# MICROCONTROLLER_RADIO.net
KiCad netlist of a schematic drawn in Altium Designer
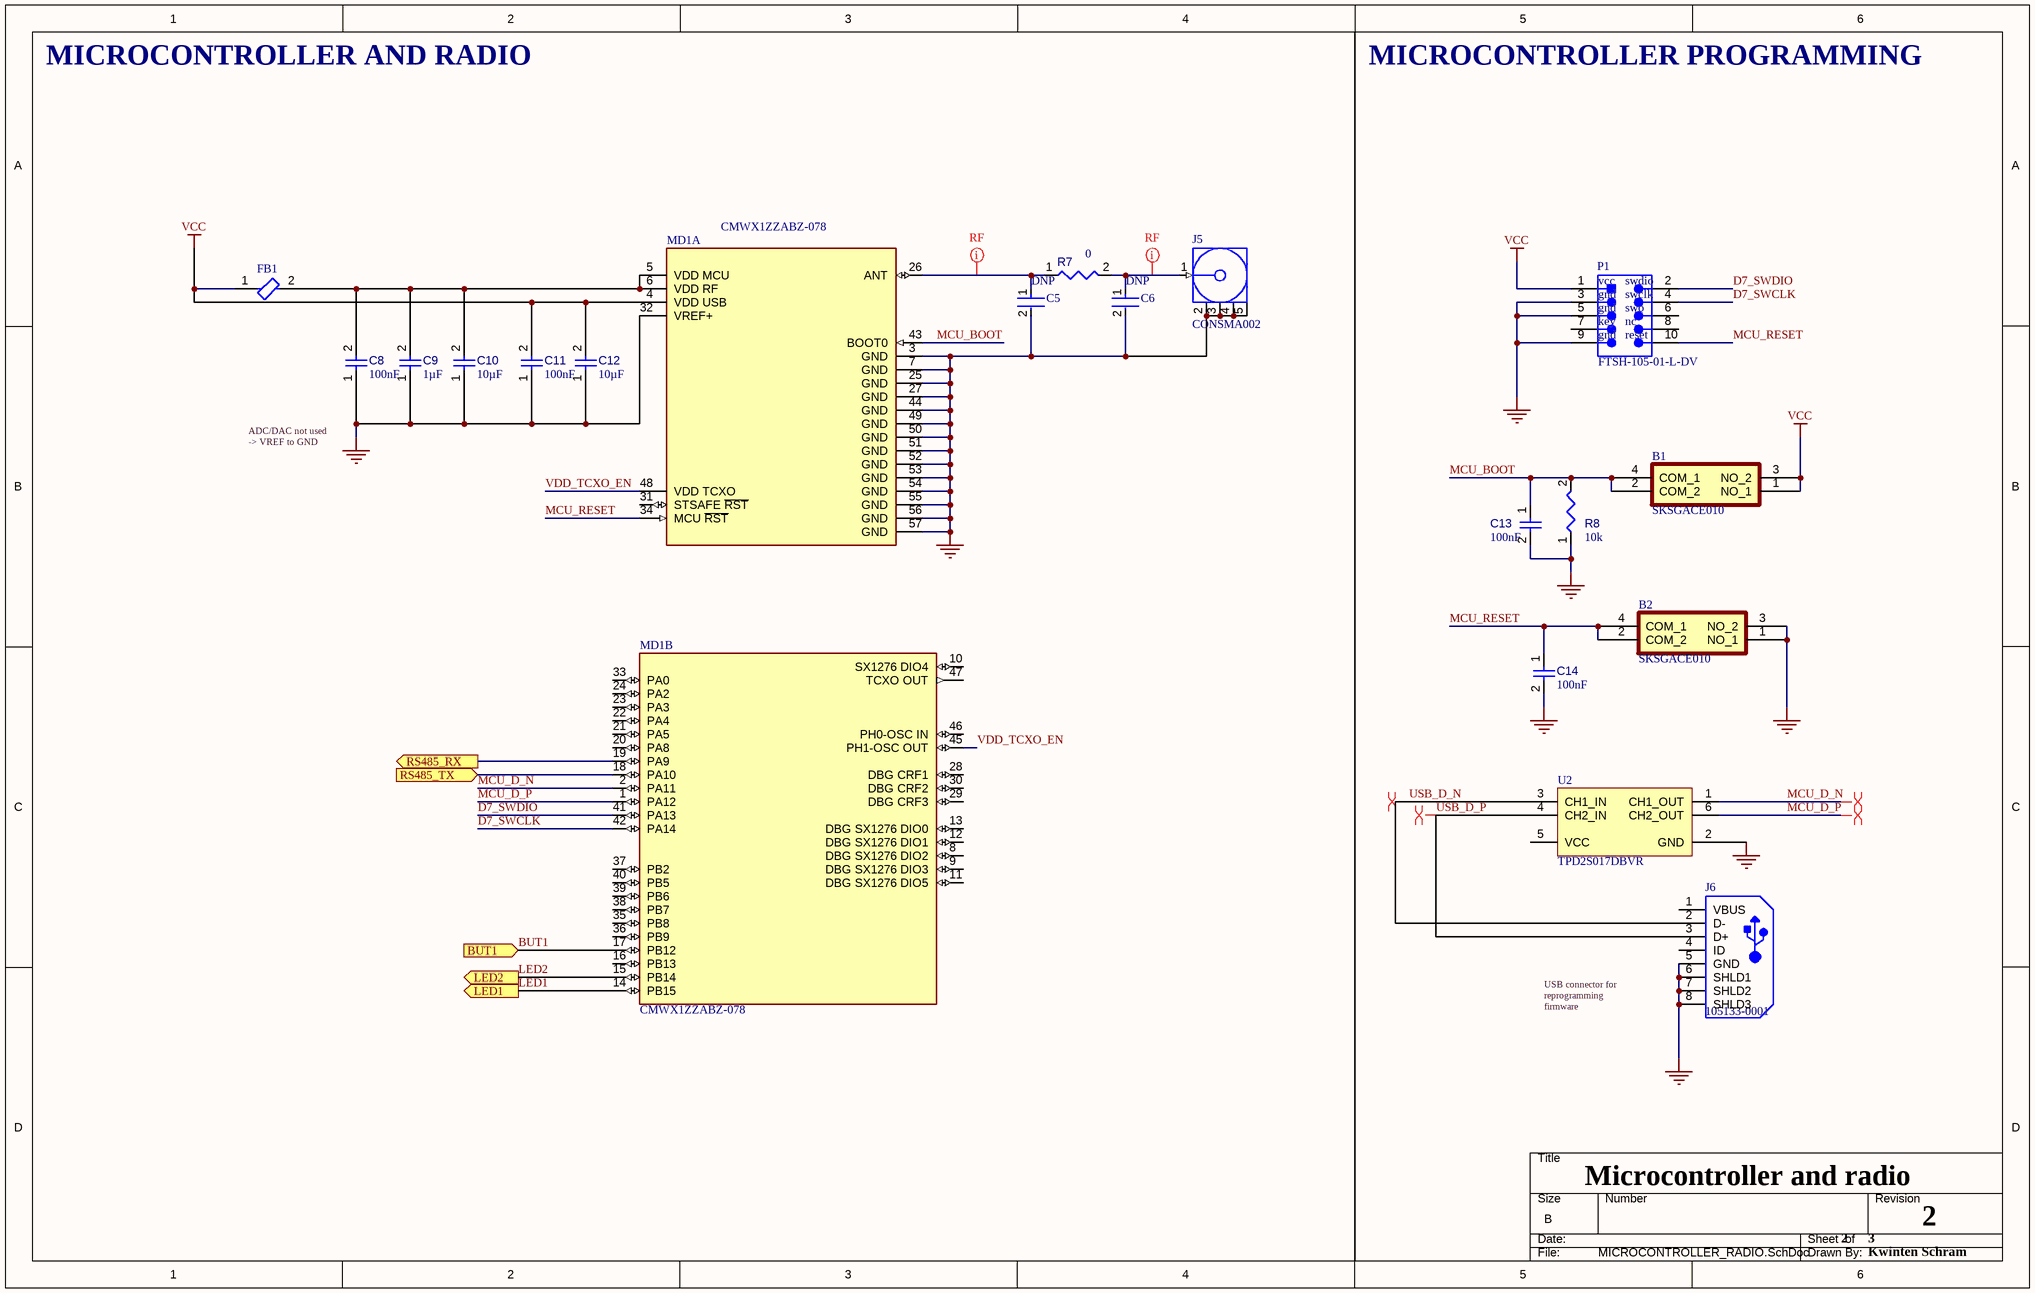
[diagram p0: MICROCONTROLLER_RADIO.SchDoc]

(export (version "E")
  (design (tool "Eeschema 10.0.6"))
  (components
    (comp (ref "B1")
      (value "SKSGACE010")
      (footprint "RKC2SJF170SMTRLFS-Footprint-1")
      (libsource (lib "Altium Concord Pro on A365") (part "RKC2SJF170SMTRLFS-Symbol-1"))
    )
    (comp (ref "B2")
      (value "SKSGACE010")
      (footprint "RKC2SJF170SMTRLFS-Footprint-1")
      (libsource (lib "Altium Concord Pro on A365") (part "RKC2SJF170SMTRLFS-Symbol-1"))
    )
    (comp (ref "C5")
      (value "CC0402KRX7R7BB104")
      (footprint "FP-CC0402-IPC_A")
      (description "CAP CER 0.1UF 16V X7R 0402")
      (fields
        (field (name "CAPACITANCE") "DNP")
        (field (name "MANUFACTURER") "YAGEO")
        (field (name "TOLERANCE") "0.1")
      )
      (libsource (lib "Altium Content Vault") (part "11868f565c42a9108669ba33697ecf6"))
    )
    (comp (ref "C6")
      (value "CC0402KRX7R7BB104")
      (footprint "FP-CC0402-IPC_A")
      (description "CAP CER 0.1UF 16V X7R 0402")
      (fields
        (field (name "CAPACITANCE") "DNP")
        (field (name "MANUFACTURER") "YAGEO")
        (field (name "TOLERANCE") "0.1")
      )
      (libsource (lib "Altium Content Vault") (part "11868f565c42a9108669ba33697ecf6"))
    )
    (comp (ref "C8")
      (value "100nF")
      (footprint "FP-0603-L_1_6_0_15-W_0_81-MFG")
      (fields (field (name "TOLERANCE") "10%") (field (name "Comment") "06033C104KAT2A"))
      (libsource (lib "Altium Concord Pro on A365") (part "CAP-NP-2"))
    )
    (comp (ref "C9")
      (value "1µF")
      (footprint "FP-CC0603-DA-MFG")
      (fields (field (name "TOLERANCE") "10%") (field (name "Comment") "CC0603KPX7R8BB105"))
      (libsource (lib "Altium Concord Pro on A365") (part "CAP-NP-2"))
    )
    (comp (ref "C10")
      (value "10µF")
      (footprint "FP-GRM188-0_1-e0_2_0_55-MFG")
      (fields (field (name "TOLERANCE") "20%") (field (name "Comment") "GRM188R60J106ME47D"))
      (libsource (lib "Altium Concord Pro on A365") (part "CAP-NP-2"))
    )
    (comp (ref "C11")
      (value "100nF")
      (footprint "FP-0603-L_1_6_0_15-W_0_81-MFG")
      (fields (field (name "TOLERANCE") "10%") (field (name "Comment") "06033C104KAT2A"))
      (libsource (lib "Altium Concord Pro on A365") (part "CAP-NP-2"))
    )
    (comp (ref "C12")
      (value "10µF")
      (footprint "FP-GRM188-0_1-e0_2_0_55-MFG")
      (fields (field (name "TOLERANCE") "20%") (field (name "Comment") "GRM188R60J106ME47D"))
      (libsource (lib "Altium Concord Pro on A365") (part "CAP-NP-2"))
    )
    (comp (ref "C13")
      (value "100nF")
      (footprint "FP-0603-L_1_6_0_15-W_0_81-MFG")
      (fields (field (name "TOLERANCE") "10%") (field (name "Comment") "06033C104KAT2A"))
      (libsource (lib "Altium Concord Pro on A365") (part "CAP-NP-2"))
    )
    (comp (ref "C14")
      (value "100nF")
      (footprint "FP-0603-L_1_6_0_15-W_0_81-MFG")
      (fields (field (name "TOLERANCE") "10%") (field (name "Comment") "06033C104KAT2A"))
      (libsource (lib "Altium Concord Pro on A365") (part "CAP-NP-2"))
    )
    (comp (ref "FB1")
      (value "BLM18AG121SN1D")
      (footprint "FP-BLM18-0_15-t0_8-IPC_B")
      (description "Chip Ferrite Bead, 0603, 120Ω @ 100MHz, 0.18Ω, 25%, 800mA")
      (fields (field (name "TOLERANCE") "25%"))
      (libsource (lib "Altium Content Vault") (part "5f30dd21d616792df468990f7003faa"))
    )
    (comp (ref "J5")
      (value "CONSMA002")
      (footprint "CON-REVSMA-RA")
      (description "RF SMA Connector")
      (libsource (lib "Altium Concord Pro on A365") (part "CN-1P-F-RF5"))
    )
    (comp (ref "J6")
      (value "105133-0001")
      (footprint "MOLX-105133-0001_V")
      (description "USB Connector, 5 Contact(s), Female, Right Angle, Surface Mount Terminal, Locking, Receptacle")
      (libsource (lib "Altium Concord Pro on A365") (part "USB-5-3SHLD"))
    )
    (comp (ref "MD1")
      (value "CMWX1ZZABZ-078")
      (footprint "FP-CMWX1ZZABZ-078-MFG")
      (description "Support Circuit, 1-Trnsvr")
      (libsource (lib "Altium Concord Pro on A365") (part "cbe14bda61ac3b1d8e6231380a7482c"))
    )
    (comp (ref "P1")
      (value "FTSH-105-01-L-DV")
      (footprint "SMTC-FTSH-105-01-L-DV_V")
      (description "Male Header, Pitch 1.27 mm, 2 x 5 Position, Height 5.96 mm, -55 to 125 degC, RoHS, Bulk")
      (fields (field (name "MANUFACTURER") "Samtec"))
      (libsource (lib "Altium Content Vault") (part "CN-2P-M-R10"))
    )
    (comp (ref "R7")
      (value "0")
      (footprint "FP-CRCW0402-e3-IPC_A")
      (description "Metal Glaze/thick Film, 0.063W, 0ohm, Surface Mount, 0402")
      (fields (field (name "POWER") "63mW") (field (name "Comment") "CRCW04020000Z0ED"))
      (libsource (lib "Altium Concord Pro on A365") (part "RES-2"))
    )
    (comp (ref "R8")
      (value "10k")
      (footprint "RESC1005X40X25NL05T10")
      (fields
        (field (name "TOLERANCE") "1%")
        (field (name "POWER") "62.5mW")
        (field (name "Comment") "RC0402FR-0710KL")
      )
      (libsource (lib "Altium Concord Pro on A365") (part "RES-2"))
    )
    (comp (ref "U2")
      (value "TPD2S017DBVR")
      (footprint "DBV0006A_N")
      (description "Trans Voltage Suppressor Diode, 5V V(RWM), Unidirectional, 4 Element, Silicon")
      (libsource (lib "Altium Concord Pro on A365") (part "TI-TPD2S017-SOT-23_DBV-6"))
    )
  )
  (nets
    (net (code "1") (name "/BUT1") (class "Default")
      (node (ref "MD1") (pin "17") (pinfunction "PB12_17") (pintype "bidirectional"))
    )
    (net (code "2") (name "/D7_SWCLK") (class "Default")
      (node (ref "MD1") (pin "42") (pinfunction "PA14_42") (pintype "bidirectional"))
      (node (ref "P1") (pin "4") (pinfunction "4_4") (pintype "passive"))
    )
    (net (code "3") (name "/D7_SWDIO") (class "Default")
      (node (ref "MD1") (pin "41") (pinfunction "PA13_41") (pintype "bidirectional"))
      (node (ref "P1") (pin "2") (pinfunction "2_2") (pintype "passive"))
    )
    (net (code "4") (name "/LED1") (class "Default")
      (node (ref "MD1") (pin "14") (pinfunction "PB15_14") (pintype "bidirectional"))
    )
    (net (code "5") (name "/LED2") (class "Default")
      (node (ref "MD1") (pin "15") (pinfunction "PB14_15") (pintype "bidirectional"))
    )
    (net (code "6") (name "/MCU_BOOT") (class "Default")
      (node (ref "B1") (pin "2") (pinfunction "COM_2_2") (pintype "passive"))
      (node (ref "B1") (pin "4") (pinfunction "COM_1_4") (pintype "passive"))
      (node (ref "C13") (pin "1") (pinfunction "1_1") (pintype "passive"))
      (node (ref "MD1") (pin "43") (pinfunction "BOOT0_43") (pintype "input"))
      (node (ref "R8") (pin "2") (pinfunction "2_2") (pintype "passive"))
    )
    (net (code "7") (name "/MCU_D_N") (class "Default")
      (node (ref "MD1") (pin "2") (pinfunction "PA11_2") (pintype "bidirectional"))
      (node (ref "U2") (pin "1") (pinfunction "CH1_OUT_1") (pintype "passive"))
    )
    (net (code "8") (name "/MCU_D_P") (class "Default")
      (node (ref "MD1") (pin "1") (pinfunction "PA12_1") (pintype "bidirectional"))
      (node (ref "U2") (pin "6") (pinfunction "CH2_OUT_6") (pintype "passive"))
    )
    (net (code "9") (name "/MCU_RESET") (class "Default")
      (node (ref "B2") (pin "2") (pinfunction "COM_2_2") (pintype "passive"))
      (node (ref "B2") (pin "4") (pinfunction "COM_1_4") (pintype "passive"))
      (node (ref "C14") (pin "1") (pinfunction "1_1") (pintype "passive"))
      (node (ref "MD1") (pin "34") (pinfunction "MCU_~{RST}_34") (pintype "input"))
      (node (ref "P1") (pin "10") (pinfunction "10_10") (pintype "passive"))
    )
    (net (code "10") (name "/RS485_RX") (class "Default")
      (node (ref "MD1") (pin "19") (pinfunction "PA9_19") (pintype "bidirectional"))
    )
    (net (code "11") (name "/RS485_TX") (class "Default")
      (node (ref "MD1") (pin "18") (pinfunction "PA10_18") (pintype "bidirectional"))
    )
    (net (code "12") (name "/USB_D_N") (class "Default")
      (node (ref "J6") (pin "2") (pinfunction "D-_2") (pintype "passive"))
      (node (ref "U2") (pin "3") (pinfunction "CH1_IN_3") (pintype "passive"))
    )
    (net (code "13") (name "/USB_D_P") (class "Default")
      (node (ref "J6") (pin "3") (pinfunction "D+_3") (pintype "passive"))
      (node (ref "U2") (pin "4") (pinfunction "CH2_IN_4") (pintype "passive"))
    )
    (net (code "14") (name "/VDD_TCXO_EN") (class "Default")
      (node (ref "MD1") (pin "45") (pinfunction "PH1-OSC_OUT_45") (pintype "bidirectional"))
      (node (ref "MD1") (pin "48") (pinfunction "VDD_TCXO_48") (pintype "power_in"))
    )
    (net (code "15") (name "GND") (class "Default")
      (node (ref "B2") (pin "1") (pinfunction "NO_1_1") (pintype "passive"))
      (node (ref "B2") (pin "3") (pinfunction "NO_2_3") (pintype "passive"))
      (node (ref "C10") (pin "1") (pinfunction "1_1") (pintype "passive"))
      (node (ref "C11") (pin "1") (pinfunction "1_1") (pintype "passive"))
      (node (ref "C12") (pin "1") (pinfunction "1_1") (pintype "passive"))
      (node (ref "C13") (pin "2") (pinfunction "2_2") (pintype "passive"))
      (node (ref "C14") (pin "2") (pinfunction "2_2") (pintype "passive"))
      (node (ref "C5") (pin "2") (pinfunction "2_2") (pintype "passive"))
      (node (ref "C6") (pin "2") (pinfunction "2_2") (pintype "passive"))
      (node (ref "C8") (pin "1") (pinfunction "1_1") (pintype "passive"))
      (node (ref "C9") (pin "1") (pinfunction "1_1") (pintype "passive"))
      (node (ref "J5") (pin "2") (pinfunction "GND_2") (pintype "power_in"))
      (node (ref "J5") (pin "3") (pinfunction "GND_3") (pintype "power_in"))
      (node (ref "J5") (pin "4") (pinfunction "GND_4") (pintype "power_in"))
      (node (ref "J5") (pin "5") (pinfunction "GND_5") (pintype "power_in"))
      (node (ref "J6") (pin "5") (pinfunction "GND_5") (pintype "passive"))
      (node (ref "J6") (pin "6") (pinfunction "SHLD1_6") (pintype "passive"))
      (node (ref "J6") (pin "7") (pinfunction "SHLD2_7") (pintype "passive"))
      (node (ref "J6") (pin "8") (pinfunction "SHLD3_8") (pintype "passive"))
      (node (ref "MD1") (pin "25") (pinfunction "GND_25") (pintype "power_in"))
      (node (ref "MD1") (pin "27") (pinfunction "GND_27") (pintype "power_in"))
      (node (ref "MD1") (pin "3") (pinfunction "GND_3") (pintype "power_in"))
      (node (ref "MD1") (pin "32") (pinfunction "VREF+_32") (pintype "power_in"))
      (node (ref "MD1") (pin "44") (pinfunction "GND_44") (pintype "power_in"))
      (node (ref "MD1") (pin "49") (pinfunction "GND_49") (pintype "power_in"))
      (node (ref "MD1") (pin "50") (pinfunction "GND_50") (pintype "power_in"))
      (node (ref "MD1") (pin "51") (pinfunction "GND_51") (pintype "power_in"))
      (node (ref "MD1") (pin "52") (pinfunction "GND_52") (pintype "power_in"))
      (node (ref "MD1") (pin "53") (pinfunction "GND_53") (pintype "power_in"))
      (node (ref "MD1") (pin "54") (pinfunction "GND_54") (pintype "power_in"))
      (node (ref "MD1") (pin "55") (pinfunction "GND_55") (pintype "power_in"))
      (node (ref "MD1") (pin "56") (pinfunction "GND_56") (pintype "power_in"))
      (node (ref "MD1") (pin "57") (pinfunction "GND_57") (pintype "power_in"))
      (node (ref "MD1") (pin "7") (pinfunction "GND_7") (pintype "power_in"))
      (node (ref "P1") (pin "3") (pinfunction "3_3") (pintype "passive"))
      (node (ref "P1") (pin "5") (pinfunction "5_5") (pintype "passive"))
      (node (ref "P1") (pin "9") (pinfunction "9_9") (pintype "passive"))
      (node (ref "R8") (pin "1") (pinfunction "1_1") (pintype "passive"))
      (node (ref "U2") (pin "2") (pinfunction "GND_2") (pintype "power_in"))
    )
    (net (code "16") (name "Net-(J5-Signal)") (class "Default")
      (node (ref "C6") (pin "1") (pinfunction "1_1") (pintype "passive"))
      (node (ref "J5") (pin "1") (pinfunction "Signal_1") (pintype "input"))
      (node (ref "R7") (pin "2") (pinfunction "2_2") (pintype "passive"))
    )
    (net (code "17") (name "Net-(MD1A-ANT)") (class "Default")
      (node (ref "C5") (pin "1") (pinfunction "1_1") (pintype "passive"))
      (node (ref "MD1") (pin "26") (pinfunction "ANT_26") (pintype "bidirectional"))
      (node (ref "R7") (pin "1") (pinfunction "1_1") (pintype "passive"))
    )
    (net (code "18") (name "Net-(MD1A-VDD_MCU)") (class "Default")
      (node (ref "C10") (pin "2") (pinfunction "2_2") (pintype "passive"))
      (node (ref "C8") (pin "2") (pinfunction "2_2") (pintype "passive"))
      (node (ref "C9") (pin "2") (pinfunction "2_2") (pintype "passive"))
      (node (ref "FB1") (pin "2") (pinfunction "2_2") (pintype "passive"))
      (node (ref "MD1") (pin "5") (pinfunction "VDD_MCU_5") (pintype "power_in"))
      (node (ref "MD1") (pin "6") (pinfunction "VDD_RF_6") (pintype "power_in"))
    )
    (net (code "19") (name "VCC") (class "Default")
      (node (ref "B1") (pin "1") (pinfunction "NO_1_1") (pintype "passive"))
      (node (ref "B1") (pin "3") (pinfunction "NO_2_3") (pintype "passive"))
      (node (ref "C11") (pin "2") (pinfunction "2_2") (pintype "passive"))
      (node (ref "C12") (pin "2") (pinfunction "2_2") (pintype "passive"))
      (node (ref "FB1") (pin "1") (pinfunction "1_1") (pintype "passive"))
      (node (ref "MD1") (pin "4") (pinfunction "VDD_USB_4") (pintype "power_in"))
      (node (ref "P1") (pin "1") (pinfunction "1_1") (pintype "passive"))
    )
    (net (code "20") (name "unconnected-(J6-ID-Pad4)") (class "Default")
      (node (ref "J6") (pin "4") (pinfunction "ID_4") (pintype "passive"))
    )
    (net (code "21") (name "unconnected-(J6-VBUS-Pad1)") (class "Default")
      (node (ref "J6") (pin "1") (pinfunction "VBUS_1") (pintype "passive"))
    )
    (net (code "22") (name "unconnected-(MD1A-STSAFE_~{RST}-Pad31)") (class "Default")
      (node (ref "MD1") (pin "31") (pinfunction "STSAFE_~{RST}_31") (pintype "bidirectional"))
    )
    (net (code "23") (name "unconnected-(MD1B-DBG_CRF1-Pad28)") (class "Default")
      (node (ref "MD1") (pin "28") (pinfunction "DBG_CRF1_28") (pintype "bidirectional"))
    )
    (net (code "24") (name "unconnected-(MD1B-DBG_CRF2-Pad30)") (class "Default")
      (node (ref "MD1") (pin "30") (pinfunction "DBG_CRF2_30") (pintype "bidirectional"))
    )
    (net (code "25") (name "unconnected-(MD1B-DBG_CRF3-Pad29)") (class "Default")
      (node (ref "MD1") (pin "29") (pinfunction "DBG_CRF3_29") (pintype "bidirectional"))
    )
    (net (code "26") (name "unconnected-(MD1B-DBG_SX1276_DIO0-Pad13)") (class "Default")
      (node (ref "MD1") (pin "13") (pinfunction "DBG_SX1276_DIO0_13") (pintype "bidirectional"))
    )
    (net (code "27") (name "unconnected-(MD1B-DBG_SX1276_DIO1-Pad12)") (class "Default")
      (node (ref "MD1") (pin "12") (pinfunction "DBG_SX1276_DIO1_12") (pintype "bidirectional"))
    )
    (net (code "28") (name "unconnected-(MD1B-DBG_SX1276_DIO2-Pad8)") (class "Default")
      (node (ref "MD1") (pin "8") (pinfunction "DBG_SX1276_DIO2_8") (pintype "bidirectional"))
    )
    (net (code "29") (name "unconnected-(MD1B-DBG_SX1276_DIO3-Pad9)") (class "Default")
      (node (ref "MD1") (pin "9") (pinfunction "DBG_SX1276_DIO3_9") (pintype "bidirectional"))
    )
    (net (code "30") (name "unconnected-(MD1B-DBG_SX1276_DIO5-Pad11)") (class "Default")
      (node (ref "MD1") (pin "11") (pinfunction "DBG_SX1276_DIO5_11") (pintype "bidirectional"))
    )
    (net (code "31") (name "unconnected-(MD1B-PA0-Pad33)") (class "Default")
      (node (ref "MD1") (pin "33") (pinfunction "PA0_33") (pintype "bidirectional"))
    )
    (net (code "32") (name "unconnected-(MD1B-PA2-Pad24)") (class "Default")
      (node (ref "MD1") (pin "24") (pinfunction "PA2_24") (pintype "bidirectional"))
    )
    (net (code "33") (name "unconnected-(MD1B-PA3-Pad23)") (class "Default")
      (node (ref "MD1") (pin "23") (pinfunction "PA3_23") (pintype "bidirectional"))
    )
    (net (code "34") (name "unconnected-(MD1B-PA4-Pad22)") (class "Default")
      (node (ref "MD1") (pin "22") (pinfunction "PA4_22") (pintype "bidirectional"))
    )
    (net (code "35") (name "unconnected-(MD1B-PA5-Pad21)") (class "Default")
      (node (ref "MD1") (pin "21") (pinfunction "PA5_21") (pintype "bidirectional"))
    )
    (net (code "36") (name "unconnected-(MD1B-PA8-Pad20)") (class "Default")
      (node (ref "MD1") (pin "20") (pinfunction "PA8_20") (pintype "bidirectional"))
    )
    (net (code "37") (name "unconnected-(MD1B-PB2-Pad37)") (class "Default")
      (node (ref "MD1") (pin "37") (pinfunction "PB2_37") (pintype "bidirectional"))
    )
    (net (code "38") (name "unconnected-(MD1B-PB5-Pad40)") (class "Default")
      (node (ref "MD1") (pin "40") (pinfunction "PB5_40") (pintype "bidirectional"))
    )
    (net (code "39") (name "unconnected-(MD1B-PB6-Pad39)") (class "Default")
      (node (ref "MD1") (pin "39") (pinfunction "PB6_39") (pintype "bidirectional"))
    )
    (net (code "40") (name "unconnected-(MD1B-PB7-Pad38)") (class "Default")
      (node (ref "MD1") (pin "38") (pinfunction "PB7_38") (pintype "bidirectional"))
    )
    (net (code "41") (name "unconnected-(MD1B-PB8-Pad35)") (class "Default")
      (node (ref "MD1") (pin "35") (pinfunction "PB8_35") (pintype "bidirectional"))
    )
    (net (code "42") (name "unconnected-(MD1B-PB9-Pad36)") (class "Default")
      (node (ref "MD1") (pin "36") (pinfunction "PB9_36") (pintype "bidirectional"))
    )
    (net (code "43") (name "unconnected-(MD1B-PB13-Pad16)") (class "Default")
      (node (ref "MD1") (pin "16") (pinfunction "PB13_16") (pintype "bidirectional"))
    )
    (net (code "44") (name "unconnected-(MD1B-PH0-OSC_IN-Pad46)") (class "Default")
      (node (ref "MD1") (pin "46") (pinfunction "PH0-OSC_IN_46") (pintype "bidirectional"))
    )
    (net (code "45") (name "unconnected-(MD1B-SX1276_DIO4-Pad10)") (class "Default")
      (node (ref "MD1") (pin "10") (pinfunction "SX1276_DIO4_10") (pintype "bidirectional"))
    )
    (net (code "46") (name "unconnected-(MD1B-TCXO_OUT-Pad47)") (class "Default")
      (node (ref "MD1") (pin "47") (pinfunction "TCXO_OUT_47") (pintype "output"))
    )
    (net (code "47") (name "unconnected-(P1-Pad6)") (class "Default")
      (node (ref "P1") (pin "6") (pinfunction "6_6") (pintype "passive"))
    )
    (net (code "48") (name "unconnected-(P1-Pad7)") (class "Default")
      (node (ref "P1") (pin "7") (pinfunction "7_7") (pintype "passive"))
    )
    (net (code "49") (name "unconnected-(P1-Pad8)") (class "Default")
      (node (ref "P1") (pin "8") (pinfunction "8_8") (pintype "passive"))
    )
    (net (code "50") (name "unconnected-(U2-VCC-Pad5)") (class "Default")
      (node (ref "U2") (pin "5") (pinfunction "VCC_5") (pintype "power_in"))
    )
  )
)
